# Embedded_Chip.net
KiCad netlist of a schematic drawn in Altium Designer
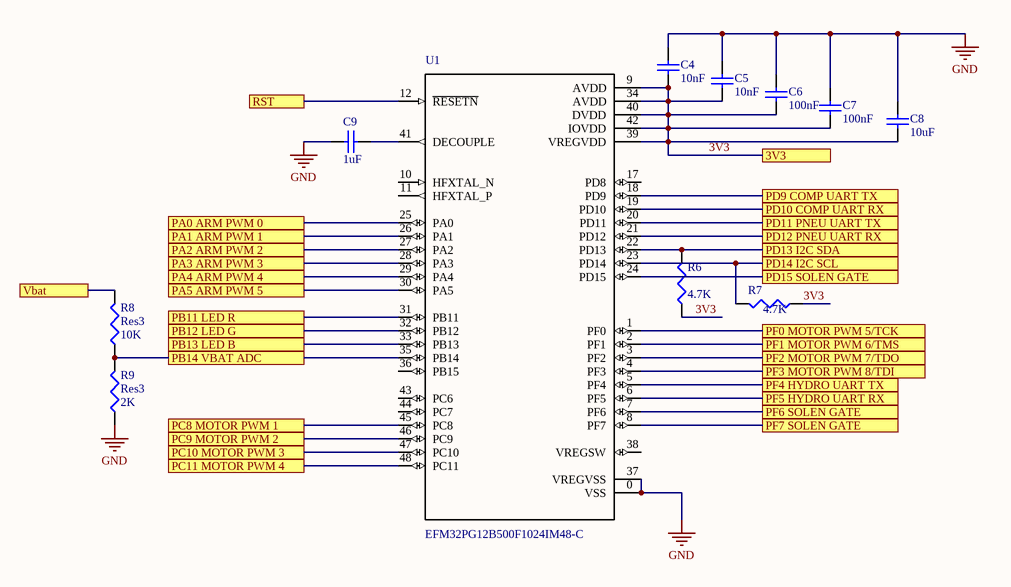
[diagram p0: Embedded_Chip.SchDoc]

(export (version "E")
  (design (tool "Eeschema 10.0.6"))
  (components
    (comp (ref "C4")
      (value "10nF")
      (footprint "C1206")
      (description "Capacitor (Semiconductor SIM Model)")
      (fields (field (name "Comment") "Cap Semi") (field (name "PUBLISHER") "Altium Limited"))
      (libsource (lib "Miscellaneous Devices") (part "Cap Semi"))
    )
    (comp (ref "C5")
      (value "10nF")
      (footprint "C1206")
      (description "Capacitor (Semiconductor SIM Model)")
      (fields (field (name "Comment") "Cap Semi") (field (name "PUBLISHER") "Altium Limited"))
      (libsource (lib "Miscellaneous Devices") (part "Cap Semi"))
    )
    (comp (ref "C6")
      (value "100nF")
      (footprint "C1206")
      (description "Capacitor (Semiconductor SIM Model)")
      (fields (field (name "Comment") "Cap Semi") (field (name "PUBLISHER") "Altium Limited"))
      (libsource (lib "Miscellaneous Devices") (part "Cap Semi"))
    )
    (comp (ref "C7")
      (value "100nF")
      (footprint "C1206")
      (description "Capacitor (Semiconductor SIM Model)")
      (fields (field (name "Comment") "Cap Semi") (field (name "PUBLISHER") "Altium Limited"))
      (libsource (lib "Miscellaneous Devices") (part "Cap Semi"))
    )
    (comp (ref "C8")
      (value "10uF")
      (footprint "C1206")
      (description "Capacitor (Semiconductor SIM Model)")
      (fields (field (name "Comment") "Cap Semi") (field (name "PUBLISHER") "Altium Limited"))
      (libsource (lib "Miscellaneous Devices") (part "Cap Semi"))
    )
    (comp (ref "C9")
      (value "1uF")
      (footprint "C1206")
      (description "Capacitor (Semiconductor SIM Model)")
      (fields (field (name "Comment") "Cap Semi") (field (name "PUBLISHER") "Altium Limited"))
      (libsource (lib "Miscellaneous Devices") (part "Cap Semi"))
    )
    (comp (ref "R6")
      (value "4.7K")
      (footprint "J1-0603")
      (description "Resistor")
      (fields (field (name "Comment") "Res3") (field (name "PUBLISHER") "Altium Limited"))
      (libsource (lib "Miscellaneous Devices") (part "Res3"))
    )
    (comp (ref "R7")
      (value "4.7K")
      (footprint "J1-0603")
      (description "Resistor")
      (fields (field (name "Comment") "Res3") (field (name "PUBLISHER") "Altium Limited"))
      (libsource (lib "Miscellaneous Devices") (part "Res3"))
    )
    (comp (ref "R8")
      (value "Res3")
      (footprint "J1-0603")
      (description "Resistor")
      (fields (field (name "ALTIUM_VALUE") "10K") (field (name "PUBLISHER") "Altium Limited"))
      (libsource (lib "Miscellaneous Devices") (part "Res3"))
    )
    (comp (ref "R9")
      (value "Res3")
      (footprint "J1-0603")
      (description "Resistor")
      (fields (field (name "ALTIUM_VALUE") "2K") (field (name "PUBLISHER") "Altium Limited"))
      (libsource (lib "Miscellaneous Devices") (part "Res3"))
    )
    (comp (ref "U1")
      (value "EFM32PG12B500F1024IM48-C")
      (footprint "QFN50P700X700X90-49N")
      (description "ARM® Cortex®-M4 Pearl Gecko Microcontroller IC 32-Bit 40MHz 1MB (1M x 8) FLASH 48-QFN (7x7)")
      (fields (field (name "MP") "EFM32PG12B500F1024GM48-B") (field (name "MF") "Silicon Labs"))
      (libsource (lib "Power_Embedded_Board_Library") (part "EFM32PG12B500F1024IM48-C"))
    )
  )
  (nets
    (net (code "1") (name "/3V3") (class "Default")
      (node (ref "C4") (pin "2") (pinfunction "2_2") (pintype "passive"))
      (node (ref "C5") (pin "2") (pinfunction "2_2") (pintype "passive"))
      (node (ref "C6") (pin "2") (pinfunction "2_2") (pintype "passive"))
      (node (ref "C7") (pin "2") (pinfunction "2_2") (pintype "passive"))
      (node (ref "C8") (pin "2") (pinfunction "2_2") (pintype "passive"))
      (node (ref "R6") (pin "1") (pinfunction "1_1") (pintype "passive"))
      (node (ref "R7") (pin "1") (pinfunction "1_1") (pintype "passive"))
      (node (ref "U1") (pin "34") (pinfunction "AVDD_34") (pintype "power_in"))
      (node (ref "U1") (pin "39") (pinfunction "VREGVDD_39") (pintype "power_in"))
      (node (ref "U1") (pin "40") (pinfunction "DVDD_40") (pintype "power_in"))
      (node (ref "U1") (pin "42") (pinfunction "IOVDD_42") (pintype "power_in"))
      (node (ref "U1") (pin "9") (pinfunction "AVDD_9") (pintype "power_in"))
    )
    (net (code "2") (name "/PA0 ARM PWM 0") (class "Default")
      (node (ref "U1") (pin "25") (pinfunction "PA0_25") (pintype "bidirectional"))
    )
    (net (code "3") (name "/PA1 ARM PWM 1") (class "Default")
      (node (ref "U1") (pin "26") (pinfunction "PA1_26") (pintype "bidirectional"))
    )
    (net (code "4") (name "/PA2 ARM PWM 2") (class "Default")
      (node (ref "U1") (pin "27") (pinfunction "PA2_27") (pintype "bidirectional"))
    )
    (net (code "5") (name "/PA3 ARM PWM 3") (class "Default")
      (node (ref "U1") (pin "28") (pinfunction "PA3_28") (pintype "bidirectional"))
    )
    (net (code "6") (name "/PA4 ARM PWM 4") (class "Default")
      (node (ref "U1") (pin "29") (pinfunction "PA4_29") (pintype "bidirectional"))
    )
    (net (code "7") (name "/PA5 ARM PWM 5") (class "Default")
      (node (ref "U1") (pin "30") (pinfunction "PA5_30") (pintype "bidirectional"))
    )
    (net (code "8") (name "/PB11 LED R") (class "Default")
      (node (ref "U1") (pin "31") (pinfunction "PB11_31") (pintype "bidirectional"))
    )
    (net (code "9") (name "/PB12 LED G") (class "Default")
      (node (ref "U1") (pin "32") (pinfunction "PB12_32") (pintype "bidirectional"))
    )
    (net (code "10") (name "/PB13 LED B") (class "Default")
      (node (ref "U1") (pin "33") (pinfunction "PB13_33") (pintype "bidirectional"))
    )
    (net (code "11") (name "/PB14 VBAT ADC") (class "Default")
      (node (ref "R8") (pin "1") (pinfunction "1_1") (pintype "passive"))
      (node (ref "R9") (pin "2") (pinfunction "2_2") (pintype "passive"))
      (node (ref "U1") (pin "35") (pinfunction "PB14_35") (pintype "bidirectional"))
    )
    (net (code "12") (name "/PC8 MOTOR PWM 1") (class "Default")
      (node (ref "U1") (pin "45") (pinfunction "PC8_45") (pintype "bidirectional"))
    )
    (net (code "13") (name "/PC9 MOTOR PWM 2") (class "Default")
      (node (ref "U1") (pin "46") (pinfunction "PC9_46") (pintype "bidirectional"))
    )
    (net (code "14") (name "/PC10 MOTOR PWM 3") (class "Default")
      (node (ref "U1") (pin "47") (pinfunction "PC10_47") (pintype "bidirectional"))
    )
    (net (code "15") (name "/PC11 MOTOR PWM 4") (class "Default")
      (node (ref "U1") (pin "48") (pinfunction "PC11_48") (pintype "bidirectional"))
    )
    (net (code "16") (name "/PD9 COMP UART TX") (class "Default")
      (node (ref "U1") (pin "18") (pinfunction "PD9_18") (pintype "bidirectional"))
    )
    (net (code "17") (name "/PD10 COMP UART RX") (class "Default")
      (node (ref "U1") (pin "19") (pinfunction "PD10_19") (pintype "bidirectional"))
    )
    (net (code "18") (name "/PD11 PNEU UART TX") (class "Default")
      (node (ref "U1") (pin "20") (pinfunction "PD11_20") (pintype "bidirectional"))
    )
    (net (code "19") (name "/PD12 PNEU UART RX") (class "Default")
      (node (ref "U1") (pin "21") (pinfunction "PD12_21") (pintype "bidirectional"))
    )
    (net (code "20") (name "/PD13 I2C SDA") (class "Default")
      (node (ref "R6") (pin "2") (pinfunction "2_2") (pintype "passive"))
      (node (ref "U1") (pin "22") (pinfunction "PD13_22") (pintype "bidirectional"))
    )
    (net (code "21") (name "/PD14 I2C SCL") (class "Default")
      (node (ref "R7") (pin "2") (pinfunction "2_2") (pintype "passive"))
      (node (ref "U1") (pin "23") (pinfunction "PD14_23") (pintype "bidirectional"))
    )
    (net (code "22") (name "/PD15 SOLEN GATE") (class "Default")
      (node (ref "U1") (pin "24") (pinfunction "PD15_24") (pintype "bidirectional"))
    )
    (net (code "23") (name "/PF0 MOTOR PWM 5{slash}TCK") (class "Default")
      (node (ref "U1") (pin "1") (pinfunction "PF0_1") (pintype "bidirectional"))
    )
    (net (code "24") (name "/PF1 MOTOR PWM 6{slash}TMS") (class "Default")
      (node (ref "U1") (pin "2") (pinfunction "PF1_2") (pintype "bidirectional"))
    )
    (net (code "25") (name "/PF2 MOTOR PWM 7{slash}TDO") (class "Default")
      (node (ref "U1") (pin "3") (pinfunction "PF2_3") (pintype "bidirectional"))
    )
    (net (code "26") (name "/PF3 MOTOR PWM 8{slash}TDI") (class "Default")
      (node (ref "U1") (pin "4") (pinfunction "PF3_4") (pintype "bidirectional"))
    )
    (net (code "27") (name "/PF4 HYDRO UART TX") (class "Default")
      (node (ref "U1") (pin "5") (pinfunction "PF4_5") (pintype "bidirectional"))
    )
    (net (code "28") (name "/PF5 HYDRO UART RX") (class "Default")
      (node (ref "U1") (pin "6") (pinfunction "PF5_6") (pintype "bidirectional"))
    )
    (net (code "29") (name "/PF6 SOLEN GATE") (class "Default")
      (node (ref "U1") (pin "7") (pinfunction "PF6_7") (pintype "bidirectional"))
    )
    (net (code "30") (name "/PF7 SOLEN GATE") (class "Default")
      (node (ref "U1") (pin "8") (pinfunction "PF7_8") (pintype "bidirectional"))
    )
    (net (code "31") (name "/RST") (class "Default")
      (node (ref "U1") (pin "12") (pinfunction "~{RESETN}_12") (pintype "input"))
    )
    (net (code "32") (name "/Vbat") (class "Default")
      (node (ref "R8") (pin "2") (pinfunction "2_2") (pintype "passive"))
    )
    (net (code "33") (name "GND") (class "Default")
      (node (ref "C4") (pin "1") (pinfunction "1_1") (pintype "passive"))
      (node (ref "C5") (pin "1") (pinfunction "1_1") (pintype "passive"))
      (node (ref "C6") (pin "1") (pinfunction "1_1") (pintype "passive"))
      (node (ref "C7") (pin "1") (pinfunction "1_1") (pintype "passive"))
      (node (ref "C8") (pin "1") (pinfunction "1_1") (pintype "passive"))
      (node (ref "C9") (pin "2") (pinfunction "2_2") (pintype "passive"))
      (node (ref "R9") (pin "1") (pinfunction "1_1") (pintype "passive"))
      (node (ref "U1") (pin "0") (pinfunction "VSS_0") (pintype "power_in"))
      (node (ref "U1") (pin "37") (pinfunction "VREGVSS_37") (pintype "power_in"))
    )
    (net (code "34") (name "Net-(U1-DECOUPLE)") (class "Default")
      (node (ref "C9") (pin "1") (pinfunction "1_1") (pintype "passive"))
      (node (ref "U1") (pin "41") (pinfunction "DECOUPLE_41") (pintype "output"))
    )
    (net (code "35") (name "unconnected-(U1-HFXTAL_N-Pad10)") (class "Default")
      (node (ref "U1") (pin "10") (pinfunction "HFXTAL_N_10") (pintype "input"))
    )
    (net (code "36") (name "unconnected-(U1-HFXTAL_P-Pad11)") (class "Default")
      (node (ref "U1") (pin "11") (pinfunction "HFXTAL_P_11") (pintype "output"))
    )
    (net (code "37") (name "unconnected-(U1-PB15-Pad36)") (class "Default")
      (node (ref "U1") (pin "36") (pinfunction "PB15_36") (pintype "bidirectional"))
    )
    (net (code "38") (name "unconnected-(U1-PC6-Pad43)") (class "Default")
      (node (ref "U1") (pin "43") (pinfunction "PC6_43") (pintype "bidirectional"))
    )
    (net (code "39") (name "unconnected-(U1-PC7-Pad44)") (class "Default")
      (node (ref "U1") (pin "44") (pinfunction "PC7_44") (pintype "bidirectional"))
    )
    (net (code "40") (name "unconnected-(U1-PD8-Pad17)") (class "Default")
      (node (ref "U1") (pin "17") (pinfunction "PD8_17") (pintype "bidirectional"))
    )
    (net (code "41") (name "unconnected-(U1-VREGSW-Pad38)") (class "Default")
      (node (ref "U1") (pin "38") (pinfunction "VREGSW_38") (pintype "bidirectional"))
    )
  )
)
